# sheet_buck.net
KiCad netlist of a schematic drawn in Altium Designer
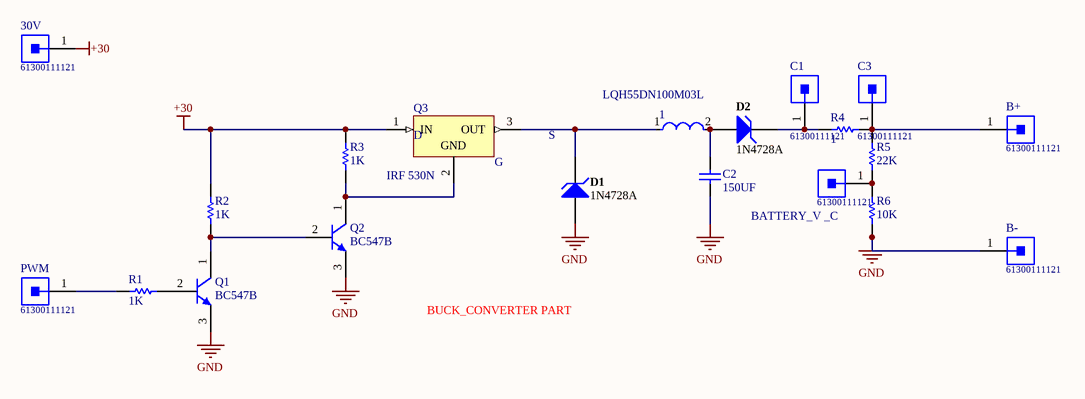
[diagram p0: sheet_buck.SchDoc]

(export (version "E")
  (design (tool "Eeschema 10.0.6"))
  (components
    (comp (ref "1")
      (value "LQH55DN100M03L")
      (footprint "FP-LQH55DN_03-MFG")
      (description "FIXED IND 10UH 1.7A 93 MOHM SMD")
      (fields (field (name "TOLERANCE") "20%"))
      (libsource (lib "Altium Content Vault") (part "725321dda6339637d4d059423bc1c3c"))
    )
    (comp (ref "30V")
      (value "61300111121")
      (footprint "61300111121")
      (description "THT Vertical Pin Header WR-PHD, Pitch 2.54 mm, Single Row, 1 pins")
      (fields (field (name "MANUFACTURER") "Wurth Elektronik") (field (name "PUBLISHER") "WurthElektronik"))
      (libsource (lib "") (part "WE-CN-1P-M-R1_2"))
    )
    (comp (ref "B+")
      (value "61300111121")
      (footprint "61300111121")
      (description "THT Vertical Pin Header WR-PHD, Pitch 2.54 mm, Single Row, 1 pins")
      (fields (field (name "MANUFACTURER") "Wurth Elektronik") (field (name "PUBLISHER") "WurthElektronik"))
      (libsource (lib "Altium Content Vault") (part "WE-CN-1P-M-R1"))
    )
    (comp (ref "B-")
      (value "61300111121")
      (footprint "61300111121")
      (description "THT Vertical Pin Header WR-PHD, Pitch 2.54 mm, Single Row, 1 pins")
      (fields (field (name "MANUFACTURER") "Wurth Elektronik") (field (name "PUBLISHER") "WurthElektronik"))
      (libsource (lib "Altium Content Vault") (part "WE-CN-1P-M-R1"))
    )
    (comp (ref "BATTERY_V _C")
      (value "61300111121")
      (footprint "61300111121")
      (description "THT Vertical Pin Header WR-PHD, Pitch 2.54 mm, Single Row, 1 pins")
      (fields (field (name "MANUFACTURER") "Wurth Elektronik") (field (name "PUBLISHER") "WurthElektronik"))
      (libsource (lib "") (part "WE-CN-1P-M-R1_2"))
    )
    (comp (ref "C1")
      (value "61300111121")
      (footprint "61300111121")
      (description "THT Vertical Pin Header WR-PHD, Pitch 2.54 mm, Single Row, 1 pins")
      (fields (field (name "MANUFACTURER") "Wurth Elektronik") (field (name "PUBLISHER") "WurthElektronik"))
      (libsource (lib "") (part "WE-CN-1P-M-R1_1"))
    )
    (comp (ref "C2")
      (value "150UF")
      (footprint "KEMT-C315-THT-2")
      (description "Capacitor, Ceramic, 0.01 uF, +/- 10%, 100 V, X7R, -55 to 125 degC, 2-Pin THD, RoHS, Bulk")
      (libsource (lib "Altium Content Vault") (part "CAP-NP-2"))
    )
    (comp (ref "C3")
      (value "61300111121")
      (footprint "61300111121")
      (description "THT Vertical Pin Header WR-PHD, Pitch 2.54 mm, Single Row, 1 pins")
      (fields (field (name "MANUFACTURER") "Wurth Elektronik") (field (name "PUBLISHER") "WurthElektronik"))
      (libsource (lib "") (part "WE-CN-1P-M-R1_1"))
    )
    (comp (ref "D1")
      (value "1N4728A")
      (footprint "FAIR-DO-41-2_V")
      (description "Zener Diode, 3.3V, 1W, 5%, -65 to 200 degC, 2-Pin DO-41, Body 2.72 x 5.2 mm, RoHS")
      (fields (field (name "MANUFACTURER") "Fairchild Semiconductor") (field (name "TOLERANCE") "5%"))
      (libsource (lib "Altium Content Vault") (part "FAIR-DZEN-A1K2-2"))
    )
    (comp (ref "D2")
      (value "1N4728A")
      (footprint "FAIR-DO-41-2_V")
      (description "Zener Diode, 3.3V, 1W, 5%, -65 to 200 degC, 2-Pin DO-41, Body 2.72 x 5.2 mm, RoHS")
      (fields (field (name "MANUFACTURER") "Fairchild Semiconductor") (field (name "TOLERANCE") "5%"))
      (libsource (lib "Altium Content Vault") (part "FAIR-DZEN-A1K2-2"))
    )
    (comp (ref "PWM")
      (value "61300111121")
      (footprint "61300111121")
      (description "THT Vertical Pin Header WR-PHD, Pitch 2.54 mm, Single Row, 1 pins")
      (fields (field (name "MANUFACTURER") "Wurth Elektronik") (field (name "PUBLISHER") "WurthElektronik"))
      (libsource (lib "") (part "WE-CN-1P-M-R1_2"))
    )
    (comp (ref "Q1")
      (value "BC547B")
      (footprint "ONSC-TO-92-3-29-11")
      (description "Amplifier Transistor, NPN Silicon, 3-Pin TO-92, Bulk Box")
      (fields (field (name "MANUFACTURER") "On Semiconductor"))
      (libsource (lib "Altium Content Vault") (part "ONSC-NPN-C1B2E3-3"))
    )
    (comp (ref "Q2")
      (value "BC547B")
      (footprint "ONSC-TO-92-3-29-11")
      (description "Amplifier Transistor, NPN Silicon, 3-Pin TO-92, Bulk Box")
      (fields (field (name "MANUFACTURER") "On Semiconductor"))
      (libsource (lib "Altium Content Vault") (part "ONSC-NPN-C1B2E3-3"))
    )
    (comp (ref "Q3")
      (value "IRF 530N")
      (footprint "FAIR-TO-220-3")
      (description "Positive Voltage Regulator, 5 V, 1 A, -40 to 125 degC, 3-Pin TO-220, RoHS, Tube")
      (fields (field (name "MANUFACTURER") "FairchildSemiconductor"))
      (libsource (lib "Altium Content Vault") (part "FAIR-LM7805CT-TO220-3"))
    )
    (comp (ref "R1")
      (value "1K")
      (footprint "RESA60-630X240")
      (description "Axial Resistor, 1 KOhm, +/- 1%, 250 mW, -55 to 155 degC, 2-Pin THD, RoHS, Bulk")
      (fields (field (name "TOLERANCE") "1%"))
      (libsource (lib "Altium Content Vault") (part "RES-2"))
    )
    (comp (ref "R2")
      (value "1K")
      (footprint "RESA60-630X240")
      (description "Axial Resistor, 1 KOhm, +/- 1%, 250 mW, -55 to 155 degC, 2-Pin THD, RoHS, Bulk")
      (fields (field (name "TOLERANCE") "1%"))
      (libsource (lib "Altium Content Vault") (part "RES-2"))
    )
    (comp (ref "R3")
      (value "1K")
      (footprint "RESA60-630X240")
      (description "Axial Resistor, 1 KOhm, +/- 1%, 250 mW, -55 to 155 degC, 2-Pin THD, RoHS, Bulk")
      (fields (field (name "TOLERANCE") "1%"))
      (libsource (lib "Altium Content Vault") (part "RES-2"))
    )
    (comp (ref "R4")
      (value "1")
      (footprint "RESA60-630X240")
      (description "Axial Resistor, 1 KOhm, +/- 1%, 250 mW, -55 to 155 degC, 2-Pin THD, RoHS, Bulk")
      (fields (field (name "TOLERANCE") "1%"))
      (libsource (lib "Altium Content Vault") (part "RES-2"))
    )
    (comp (ref "R5")
      (value "22K")
      (footprint "RESA60-630X240")
      (description "Axial Resistor, 1 KOhm, +/- 1%, 250 mW, -55 to 155 degC, 2-Pin THD, RoHS, Bulk")
      (fields (field (name "TOLERANCE") "1%"))
      (libsource (lib "Altium Content Vault") (part "RES-2"))
    )
    (comp (ref "R6")
      (value "10K")
      (footprint "RESA60-630X240")
      (description "Axial Resistor, 1 KOhm, +/- 1%, 250 mW, -55 to 155 degC, 2-Pin THD, RoHS, Bulk")
      (fields (field (name "TOLERANCE") "1%"))
      (libsource (lib "Altium Content Vault") (part "RES-2"))
    )
  )
  (nets
    (net (code "1") (name "+30") (class "Default")
      (node (ref "30V") (pin "1") (pinfunction "1_1") (pintype "passive"))
      (node (ref "Q3") (pin "1") (pinfunction "IN_1") (pintype "input"))
      (node (ref "R2") (pin "2") (pinfunction "2_2") (pintype "passive"))
      (node (ref "R3") (pin "2") (pinfunction "2_2") (pintype "passive"))
    )
    (net (code "2") (name "GND") (class "Default")
      (node (ref "B-") (pin "1") (pinfunction "1_1") (pintype "passive"))
      (node (ref "C2") (pin "1") (pinfunction "1_1") (pintype "passive"))
      (node (ref "D1") (pin "1") (pinfunction "A_1") (pintype "passive"))
      (node (ref "Q1") (pin "3") (pinfunction "E_3") (pintype "passive"))
      (node (ref "Q2") (pin "3") (pinfunction "E_3") (pintype "passive"))
      (node (ref "R6") (pin "2") (pinfunction "2_2") (pintype "passive"))
    )
    (net (code "3") (name "Net-(B+-Pad1)") (class "Default")
      (node (ref "B+") (pin "1") (pinfunction "1_1") (pintype "passive"))
      (node (ref "C3") (pin "1") (pinfunction "1_1") (pintype "passive"))
      (node (ref "R4") (pin "1") (pinfunction "1_1") (pintype "passive"))
      (node (ref "R5") (pin "1") (pinfunction "1_1") (pintype "passive"))
    )
    (net (code "4") (name "Net-(BATTERY_V _C-Pad1)") (class "Default")
      (node (ref "BATTERY_V _C") (pin "1") (pinfunction "1_1") (pintype "passive"))
      (node (ref "R5") (pin "2") (pinfunction "2_2") (pintype "passive"))
      (node (ref "R6") (pin "1") (pinfunction "1_1") (pintype "passive"))
    )
    (net (code "5") (name "Net-(D1-K)") (class "Default")
      (node (ref "1") (pin "1") (pinfunction "1_1") (pintype "passive"))
      (node (ref "D1") (pin "2") (pinfunction "K_2") (pintype "passive"))
      (node (ref "Q3") (pin "3") (pinfunction "OUT_3") (pintype "output"))
    )
    (net (code "6") (name "Net-(D2-A)") (class "Default")
      (node (ref "1") (pin "2") (pinfunction "2_2") (pintype "passive"))
      (node (ref "C2") (pin "2") (pinfunction "2_2") (pintype "passive"))
      (node (ref "D2") (pin "1") (pinfunction "A_1") (pintype "passive"))
    )
    (net (code "7") (name "Net-(D2-K)") (class "Default")
      (node (ref "C1") (pin "1") (pinfunction "1_1") (pintype "passive"))
      (node (ref "D2") (pin "2") (pinfunction "K_2") (pintype "passive"))
      (node (ref "R4") (pin "2") (pinfunction "2_2") (pintype "passive"))
    )
    (net (code "8") (name "Net-(PWM-Pad1)") (class "Default")
      (node (ref "PWM") (pin "1") (pinfunction "1_1") (pintype "passive"))
      (node (ref "R1") (pin "2") (pinfunction "2_2") (pintype "passive"))
    )
    (net (code "9") (name "Net-(Q1-B)") (class "Default")
      (node (ref "Q1") (pin "2") (pinfunction "B_2") (pintype "passive"))
      (node (ref "R1") (pin "1") (pinfunction "1_1") (pintype "passive"))
    )
    (net (code "10") (name "Net-(Q1-C)") (class "Default")
      (node (ref "Q1") (pin "1") (pinfunction "C_1") (pintype "passive"))
      (node (ref "Q2") (pin "2") (pinfunction "B_2") (pintype "passive"))
      (node (ref "R2") (pin "1") (pinfunction "1_1") (pintype "passive"))
    )
    (net (code "11") (name "Net-(Q2-C)") (class "Default")
      (node (ref "Q2") (pin "1") (pinfunction "C_1") (pintype "passive"))
      (node (ref "Q3") (pin "2") (pinfunction "GND_2") (pintype "power_in"))
      (node (ref "R3") (pin "1") (pinfunction "1_1") (pintype "passive"))
    )
  )
)
